# UC_Battery_4xAA.net
KiCad netlist of a schematic drawn in EAGLE
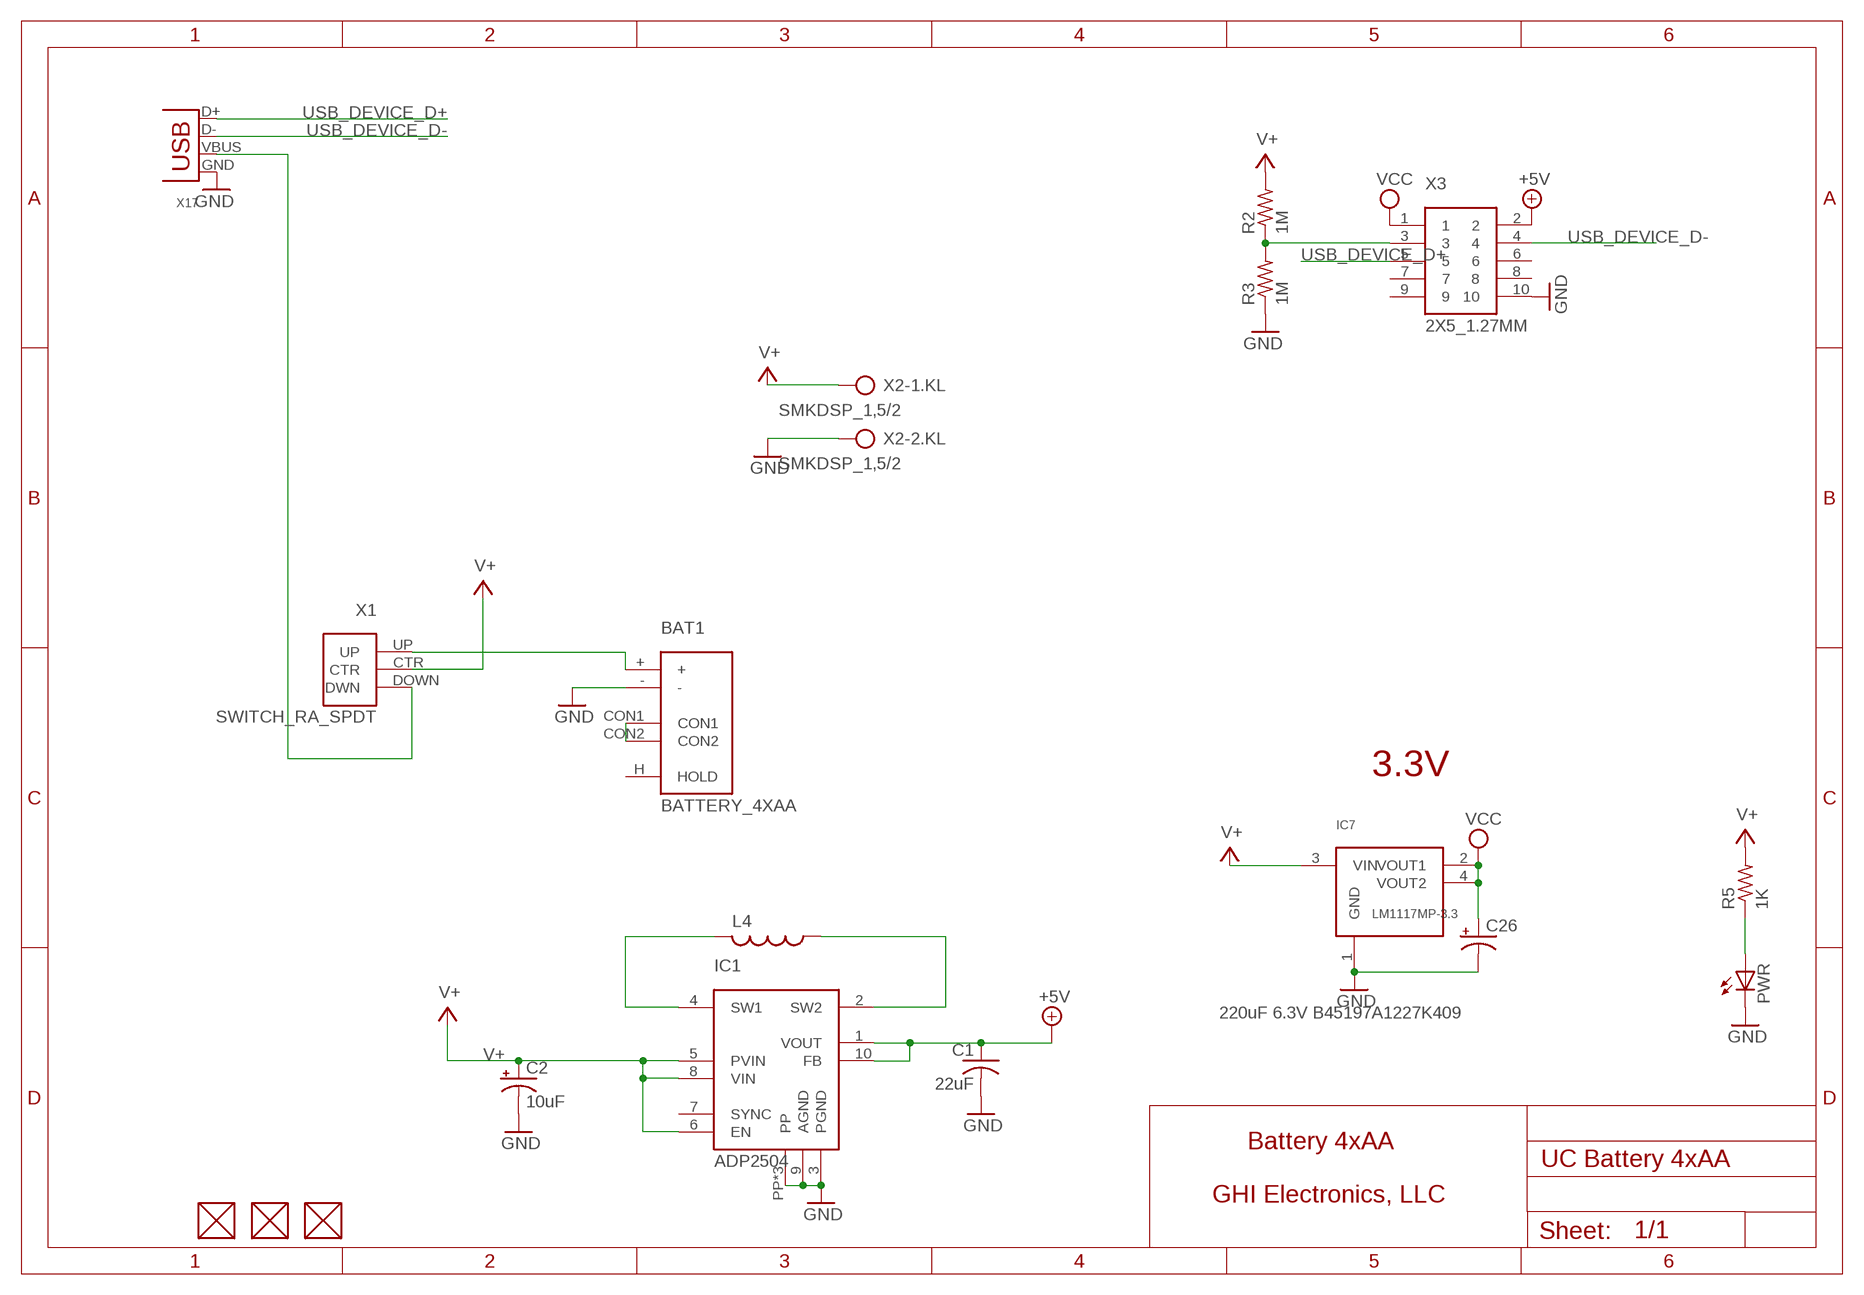
[diagram p0: schematic, sheet 1]

(export (version "E")
  (design (tool "Eeschema 10.0.6"))
  (components
    (comp (ref "BAT1")
      (value "BATTERY_4XAA")
      (footprint "eagle-import:BATTERY_4XAA")
      (libsource (lib "eagle-import") (part "BATTERY_4XAA"))
    )
    (comp (ref "C1")
      (value "22uF")
      (footprint "eagle-import:C0805K")
      (libsource (lib "eagle-import") (part "C-USC0805K"))
    )
    (comp (ref "C2")
      (value "10uF")
      (footprint "eagle-import:CT3528")
      (libsource (lib "eagle-import") (part "CPOL-USCT3528"))
    )
    (comp (ref "C26")
      (value "220uF 6.3V B45197A1227K409")
      (footprint "eagle-import:D_7343-31W")
      (libsource (lib "eagle-import") (part "CPOL-USD/7343-31W"))
    )
    (comp (ref "FUD1")
      (value "FIDUCIAL")
      (footprint "eagle-import:FIDUCIAL_40MIL")
      (libsource (lib "eagle-import") (part "FIDUCIAL"))
    )
    (comp (ref "FUD2")
      (value "FIDUCIAL")
      (footprint "eagle-import:FIDUCIAL_40MIL")
      (libsource (lib "eagle-import") (part "FIDUCIAL"))
    )
    (comp (ref "FUD3")
      (value "FIDUCIAL")
      (footprint "eagle-import:FIDUCIAL_40MIL")
      (libsource (lib "eagle-import") (part "FIDUCIAL"))
    )
    (comp (ref "IC1")
      (value "ADP2504")
      (footprint "eagle-import:QFN10_3X3")
      (libsource (lib "eagle-import") (part "ADP2504"))
    )
    (comp (ref "IC7")
      (value "LM1117MP-3.3")
      (footprint "eagle-import:SOT223")
      (libsource (lib "eagle-import") (part "LM1117"))
    )
    (comp (ref "L4")
      (value "L-USL2825P")
      (footprint "eagle-import:L2825P")
      (libsource (lib "eagle-import") (part "L-USL2825P"))
    )
    (comp (ref "PWR")
      (value "LEDCHIPLED_0805")
      (footprint "eagle-import:CHIPLED_0805")
      (libsource (lib "eagle-import") (part "LEDCHIPLED_0805"))
    )
    (comp (ref "R2")
      (value "1M")
      (footprint "eagle-import:R0603")
      (libsource (lib "eagle-import") (part "R-US_R0603"))
    )
    (comp (ref "R3")
      (value "1M")
      (footprint "eagle-import:R0603")
      (libsource (lib "eagle-import") (part "R-US_R0603"))
    )
    (comp (ref "R5")
      (value "1K")
      (footprint "eagle-import:R0603")
      (libsource (lib "eagle-import") (part "R-US_R0603"))
    )
    (comp (ref "X1")
      (value "SWITCH_RA_SPDT")
      (footprint "eagle-import:SWITCH_RA_SPDT")
      (libsource (lib "eagle-import") (part "SWITCH_RA_SPDT"))
    )
    (comp (ref "X2")
      (value "SMKDSP_1,5/2")
      (footprint "eagle-import:SMKDSP_1,5_2")
      (libsource (lib "eagle-import") (part "SMKDSP_1,5/2"))
    )
    (comp (ref "X3")
      (value "2X5_1.27MM")
      (footprint "eagle-import:2X5_1.27MM")
      (libsource (lib "eagle-import") (part "2X5_1.27MM"))
    )
    (comp (ref "X17")
      (value "DX2R005HN2E700")
      (footprint "eagle-import:USB-MB-S")
      (libsource (lib "eagle-import") (part "USB-MB-S"))
    )
  )
  (nets
    (net (code "1") (name "+5V") (class "Default")
      (node (ref "C1") (pin "1") (pinfunction "1_1") (pintype "passive"))
      (node (ref "IC1") (pin "1") (pinfunction "VOUT_1") (pintype "bidirectional"))
      (node (ref "IC1") (pin "10") (pinfunction "FB_10") (pintype "bidirectional"))
      (node (ref "X3") (pin "2") (pinfunction "2_2") (pintype "bidirectional"))
    )
    (net (code "2") (name "/USB_DEVICE_D+") (class "Default")
      (node (ref "X17") (pin "D+") (pinfunction "D+_D+") (pintype "bidirectional"))
      (node (ref "X3") (pin "5") (pinfunction "5_5") (pintype "bidirectional"))
    )
    (net (code "3") (name "/USB_DEVICE_D-") (class "Default")
      (node (ref "X17") (pin "D-") (pinfunction "D-_D-") (pintype "bidirectional"))
      (node (ref "X3") (pin "4") (pinfunction "4_4") (pintype "bidirectional"))
    )
    (net (code "4") (name "GND") (class "Default")
      (node (ref "BAT1") (pin "-") (pinfunction "-_-") (pintype "bidirectional"))
      (node (ref "C1") (pin "2") (pinfunction "2_2") (pintype "passive"))
      (node (ref "C2") (pin "-") (pinfunction "-_-") (pintype "passive"))
      (node (ref "C26") (pin "-") (pinfunction "-_-") (pintype "passive"))
      (node (ref "IC1") (pin "3") (pinfunction "PGND_3") (pintype "bidirectional"))
      (node (ref "IC1") (pin "9") (pinfunction "AGND_9") (pintype "bidirectional"))
      (node (ref "IC1") (pin "PP") (pinfunction "PP_PP") (pintype "bidirectional"))
      (node (ref "IC1") (pin "PP@1") (pinfunction "PP_PP@1") (pintype "bidirectional"))
      (node (ref "IC1") (pin "PP@2") (pinfunction "PP_PP@2") (pintype "bidirectional"))
      (node (ref "IC7") (pin "1") (pinfunction "GND_1") (pintype "bidirectional"))
      (node (ref "PWR") (pin "C") (pinfunction "C_C") (pintype "passive"))
      (node (ref "R3") (pin "1") (pinfunction "1_1") (pintype "passive"))
      (node (ref "X17") (pin "GND") (pinfunction "GND_GND") (pintype "bidirectional"))
      (node (ref "X2") (pin "2") (pinfunction "KL_2") (pintype "passive"))
      (node (ref "X3") (pin "10") (pinfunction "10_10") (pintype "bidirectional"))
    )
    (net (code "5") (name "Net-(BAT1-Pad+)") (class "Default")
      (node (ref "BAT1") (pin "+") (pinfunction "+_+") (pintype "bidirectional"))
      (node (ref "X1") (pin "UP") (pinfunction "UP_UP") (pintype "bidirectional"))
    )
    (net (code "6") (name "Net-(BAT1-PadCON1)") (class "Default")
      (node (ref "BAT1") (pin "CON1") (pinfunction "CON1_CON1") (pintype "bidirectional"))
      (node (ref "BAT1") (pin "CON2") (pinfunction "CON2_CON2") (pintype "bidirectional"))
    )
    (net (code "7") (name "Net-(IC1-SW1)") (class "Default")
      (node (ref "IC1") (pin "4") (pinfunction "SW1_4") (pintype "bidirectional"))
      (node (ref "L4") (pin "2") (pinfunction "2_2") (pintype "passive"))
    )
    (net (code "8") (name "Net-(IC1-SW2)") (class "Default")
      (node (ref "IC1") (pin "2") (pinfunction "SW2_2") (pintype "bidirectional"))
      (node (ref "L4") (pin "1") (pinfunction "1_1") (pintype "passive"))
    )
    (net (code "9") (name "Net-(PWR-PadA)") (class "Default")
      (node (ref "PWR") (pin "A") (pinfunction "A_A") (pintype "passive"))
      (node (ref "R5") (pin "1") (pinfunction "1_1") (pintype "passive"))
    )
    (net (code "10") (name "Net-(R2-Pad1)") (class "Default")
      (node (ref "R2") (pin "1") (pinfunction "1_1") (pintype "passive"))
      (node (ref "R3") (pin "2") (pinfunction "2_2") (pintype "passive"))
      (node (ref "X3") (pin "3") (pinfunction "3_3") (pintype "bidirectional"))
    )
    (net (code "11") (name "Net-(X1-DWN)") (class "Default")
      (node (ref "X1") (pin "DOWN") (pinfunction "DWN_DOWN") (pintype "bidirectional"))
      (node (ref "X17") (pin "VBUS") (pinfunction "VBUS_VBUS") (pintype "bidirectional"))
    )
    (net (code "12") (name "V+") (class "Default")
      (node (ref "C2") (pin "+") (pinfunction "+_+") (pintype "passive"))
      (node (ref "IC1") (pin "5") (pinfunction "PVIN_5") (pintype "bidirectional"))
      (node (ref "IC1") (pin "6") (pinfunction "EN_6") (pintype "bidirectional"))
      (node (ref "IC1") (pin "8") (pinfunction "VIN_8") (pintype "bidirectional"))
      (node (ref "IC7") (pin "3") (pinfunction "VIN_3") (pintype "bidirectional"))
      (node (ref "R2") (pin "2") (pinfunction "2_2") (pintype "passive"))
      (node (ref "R5") (pin "2") (pinfunction "2_2") (pintype "passive"))
      (node (ref "X1") (pin "CTR") (pinfunction "CTR_CTR") (pintype "bidirectional"))
      (node (ref "X2") (pin "1") (pinfunction "KL_1") (pintype "passive"))
    )
    (net (code "13") (name "VCC") (class "Default")
      (node (ref "C26") (pin "+") (pinfunction "+_+") (pintype "passive"))
      (node (ref "IC7") (pin "2") (pinfunction "VOUT1_2") (pintype "bidirectional"))
      (node (ref "IC7") (pin "4") (pinfunction "VOUT2_4") (pintype "bidirectional"))
      (node (ref "X3") (pin "1") (pinfunction "1_1") (pintype "bidirectional"))
    )
    (net (code "14") (name "unconnected-(BAT1-HOLD-PadH)") (class "Default")
      (node (ref "BAT1") (pin "H") (pinfunction "HOLD_H") (pintype "bidirectional"))
    )
    (net (code "15") (name "unconnected-(FUD1-PadP$1)") (class "Default")
      (node (ref "FUD1") (pin "P$1") (pinfunction "P$1_P$1") (pintype "no_connect"))
    )
    (net (code "16") (name "unconnected-(FUD2-PadP$1)") (class "Default")
      (node (ref "FUD2") (pin "P$1") (pinfunction "P$1_P$1") (pintype "no_connect"))
    )
    (net (code "17") (name "unconnected-(FUD3-PadP$1)") (class "Default")
      (node (ref "FUD3") (pin "P$1") (pinfunction "P$1_P$1") (pintype "no_connect"))
    )
    (net (code "18") (name "unconnected-(IC1-SYNC-Pad7)") (class "Default")
      (node (ref "IC1") (pin "7") (pinfunction "SYNC_7") (pintype "bidirectional"))
    )
    (net (code "19") (name "unconnected-(X3-Pad6)") (class "Default")
      (node (ref "X3") (pin "6") (pinfunction "6_6") (pintype "bidirectional"))
    )
    (net (code "20") (name "unconnected-(X3-Pad7)") (class "Default")
      (node (ref "X3") (pin "7") (pinfunction "7_7") (pintype "bidirectional"))
    )
    (net (code "21") (name "unconnected-(X3-Pad8)") (class "Default")
      (node (ref "X3") (pin "8") (pinfunction "8_8") (pintype "bidirectional"))
    )
    (net (code "22") (name "unconnected-(X3-Pad9)") (class "Default")
      (node (ref "X3") (pin "9") (pinfunction "9_9") (pintype "bidirectional"))
    )
  )
)
